# IOProtection.net
KiCad netlist of a schematic drawn in Altium Designer
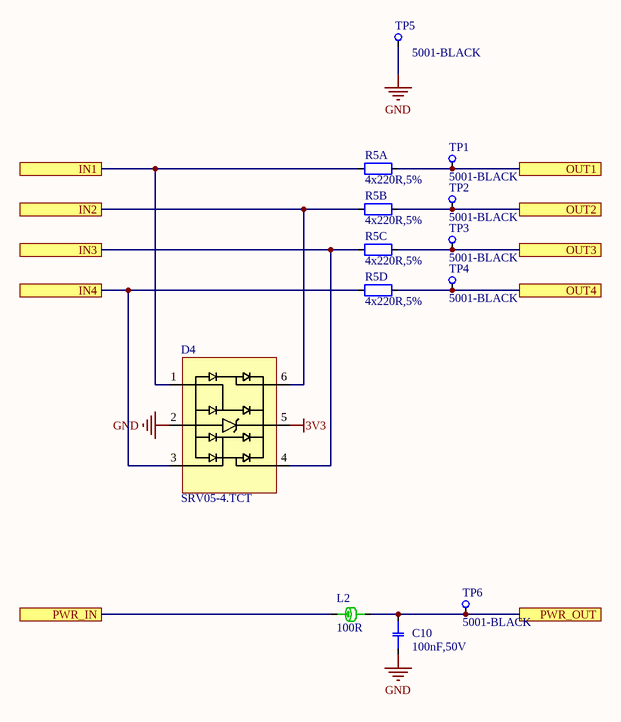
[diagram p0: IOProtection.SchDoc]

(export (version "E")
  (design (tool "Eeschema 10.0.6"))
  (components
    (comp (ref "C10")
      (value "100nF,50V")
      (footprint "CAPC1608X09N_0603")
      (description "CAP CER 0.1UF 50V 10% X7R 0603")
      (fields (field (name "MANUFACTURER") "Kemet") (field (name "TOLERANCE") "10%"))
      (libsource (lib "library") (part "CAP-NP_1"))
    )
    (comp (ref "D4")
      (value "SRV05-4.TCT")
      (footprint "SOT95P280X145-6N_SOT23-6")
      (description "IC TVS ARRAY 4-LINE 5V SOT23-6")
      (fields (field (name "MANUFACTURER") "Semtech"))
      (libsource (lib "library") (part "SRV05-4.TCT"))
    )
    (comp (ref "L2")
      (value "100R")
      (footprint "INDC1608X10N_0603")
      (description "FERRITE BEAD 100 OHM 0603 1LN")
      (fields
        (field (name "MANUFACTURER") "Murata")
        (field (name "MANUFACTURER PART NUMBER") "BLM18EG101TN1D")
      )
      (libsource (lib "library") (part "FERRITE"))
    )
    (comp (ref "R5")
      (value "4x220R,5%")
      (footprint "RESCAF80P32X16X60N")
      (description "RES ARRAY 220 OHM 8TRM 4 RES SMD")
      (fields (field (name "MANUFACTURER") "Yageo") (field (name "TOLERANCE") "5%"))
      (libsource (lib "library") (part "RESISTOR_ARRAY_4X"))
    )
    (comp (ref "TP1")
      (value "5001-BLACK")
      (footprint "TP_5002")
      (description "PC TEST LOOP BLACK")
      (fields
        (field (name "MANUFACTURER") "Keystone Electronics")
        (field (name "MANUFACTURER PART NUMBER") "5000")
      )
      (libsource (lib "library") (part "TP_1"))
    )
    (comp (ref "TP2")
      (value "5001-BLACK")
      (footprint "TP_5002")
      (description "PC TEST LOOP BLACK")
      (fields
        (field (name "MANUFACTURER") "Keystone Electronics")
        (field (name "MANUFACTURER PART NUMBER") "5000")
      )
      (libsource (lib "library") (part "TP_1"))
    )
    (comp (ref "TP3")
      (value "5001-BLACK")
      (footprint "TP_5002")
      (description "PC TEST LOOP BLACK")
      (fields
        (field (name "MANUFACTURER") "Keystone Electronics")
        (field (name "MANUFACTURER PART NUMBER") "5000")
      )
      (libsource (lib "library") (part "TP_1"))
    )
    (comp (ref "TP4")
      (value "5001-BLACK")
      (footprint "TP_5002")
      (description "PC TEST LOOP BLACK")
      (fields
        (field (name "MANUFACTURER") "Keystone Electronics")
        (field (name "MANUFACTURER PART NUMBER") "5000")
      )
      (libsource (lib "library") (part "TP_1"))
    )
    (comp (ref "TP5")
      (value "5001-BLACK")
      (footprint "TP_5002")
      (description "PC TEST LOOP BLACK")
      (fields
        (field (name "MANUFACTURER") "Keystone Electronics")
        (field (name "MANUFACTURER PART NUMBER") "5000")
      )
      (libsource (lib "library") (part "TP_1"))
    )
    (comp (ref "TP6")
      (value "5001-BLACK")
      (footprint "TP_5002")
      (description "PC TEST LOOP BLACK")
      (fields
        (field (name "MANUFACTURER") "Keystone Electronics")
        (field (name "MANUFACTURER PART NUMBER") "5000")
      )
      (libsource (lib "library") (part "TP_1"))
    )
  )
  (nets
    (net (code "1") (name "/IN1") (class "Default")
      (node (ref "D4") (pin "1") (pinfunction "1_1") (pintype "passive"))
      (node (ref "R5") (pin "1") (pinfunction "1_1") (pintype "passive"))
    )
    (net (code "2") (name "/IN2") (class "Default")
      (node (ref "D4") (pin "6") (pinfunction "6_6") (pintype "passive"))
      (node (ref "R5") (pin "2") (pinfunction "2_2") (pintype "passive"))
    )
    (net (code "3") (name "/IN3") (class "Default")
      (node (ref "D4") (pin "4") (pinfunction "4_4") (pintype "passive"))
      (node (ref "R5") (pin "3") (pinfunction "3_3") (pintype "passive"))
    )
    (net (code "4") (name "/IN4") (class "Default")
      (node (ref "D4") (pin "3") (pinfunction "3_3") (pintype "passive"))
      (node (ref "R5") (pin "4") (pinfunction "4_4") (pintype "passive"))
    )
    (net (code "5") (name "/OUT1") (class "Default")
      (node (ref "R5") (pin "8") (pinfunction "8_8") (pintype "passive"))
      (node (ref "TP1") (pin "1") (pinfunction "1_1") (pintype "passive"))
    )
    (net (code "6") (name "/OUT2") (class "Default")
      (node (ref "R5") (pin "7") (pinfunction "7_7") (pintype "passive"))
      (node (ref "TP2") (pin "1") (pinfunction "1_1") (pintype "passive"))
    )
    (net (code "7") (name "/OUT3") (class "Default")
      (node (ref "R5") (pin "6") (pinfunction "6_6") (pintype "passive"))
      (node (ref "TP3") (pin "1") (pinfunction "1_1") (pintype "passive"))
    )
    (net (code "8") (name "/OUT4") (class "Default")
      (node (ref "R5") (pin "5") (pinfunction "5_5") (pintype "passive"))
      (node (ref "TP4") (pin "1") (pinfunction "1_1") (pintype "passive"))
    )
    (net (code "9") (name "/PWR_IN") (class "Default") (node (ref "L2") (pin "1") (pintype "passive")))
    (net (code "10") (name "/PWR_OUT") (class "Default")
      (node (ref "C10") (pin "2") (pinfunction "2_2") (pintype "passive"))
      (node (ref "L2") (pin "2") (pintype "passive"))
      (node (ref "TP6") (pin "1") (pinfunction "1_1") (pintype "passive"))
    )
    (net (code "11") (name "3V3") (class "Default")
      (node (ref "D4") (pin "5") (pinfunction "5_5") (pintype "passive"))
    )
    (net (code "12") (name "GND") (class "Default")
      (node (ref "C10") (pin "1") (pinfunction "1_1") (pintype "passive"))
      (node (ref "D4") (pin "2") (pinfunction "2_2") (pintype "passive"))
      (node (ref "TP5") (pin "1") (pinfunction "1_1") (pintype "passive"))
    )
  )
)
